# Power.net
KiCad netlist of a schematic drawn in Altium Designer
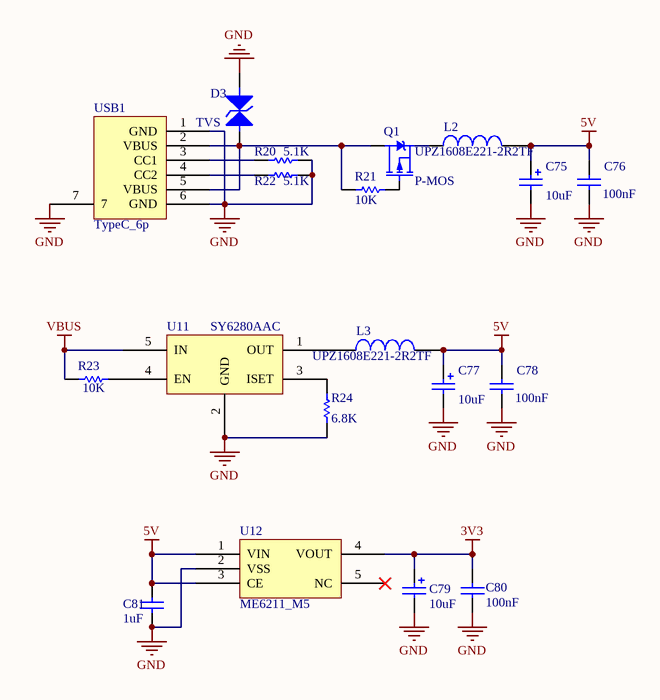
[diagram p0: Power.SchDoc]

(export (version "E")
  (design (tool "Eeschema 10.0.6"))
  (components
    (comp (ref "C75")
      (value "10uF")
      (footprint "电容:TAJ-A/3216")
      (description "Polarized Capacitor (Axial)")
      (fields (field (name "Comment") "Cap Pol2") (field (name "PUBLISHER") "Altium Limited"))
      (libsource (lib "Miscellaneous Devices") (part "Cap Pol2"))
    )
    (comp (ref "C76")
      (value "100nF")
      (footprint "C0603_M")
      (description "Capacitor")
      (fields (field (name "Comment") "Cap") (field (name "PUBLISHER") "Altium Limited"))
      (libsource (lib "Miscellaneous Devices") (part "Cap"))
    )
    (comp (ref "C77")
      (value "10uF")
      (footprint "电容:TAJ-A/3216")
      (description "Polarized Capacitor (Axial)")
      (fields (field (name "Comment") "Cap Pol2") (field (name "PUBLISHER") "Altium Limited"))
      (libsource (lib "Miscellaneous Devices") (part "Cap Pol2"))
    )
    (comp (ref "C78")
      (value "100nF")
      (footprint "C0603_M")
      (description "Capacitor")
      (fields (field (name "Comment") "Cap") (field (name "PUBLISHER") "Altium Limited"))
      (libsource (lib "Miscellaneous Devices") (part "Cap"))
    )
    (comp (ref "C79")
      (value "10uF")
      (footprint "TAJ-A/3216")
      (description "Polarized Capacitor (Axial)")
      (fields (field (name "Comment") "Cap Pol2") (field (name "PUBLISHER") "Altium Limited"))
      (libsource (lib "Miscellaneous Devices") (part "Cap Pol2"))
    )
    (comp (ref "C80")
      (value "100nF")
      (footprint "C0603_M")
      (description "Capacitor")
      (fields (field (name "Comment") "Cap") (field (name "PUBLISHER") "Altium Limited"))
      (libsource (lib "Miscellaneous Devices") (part "Cap"))
    )
    (comp (ref "C81")
      (value "1uF")
      (footprint "C0603_M")
      (description "Capacitor")
      (fields (field (name "Comment") "Cap") (field (name "PUBLISHER") "Altium Limited"))
      (libsource (lib "Miscellaneous Devices") (part "Cap"))
    )
    (comp (ref "D3")
      (value "TVS")
      (footprint "SOD-123")
      (description "双向瞬态抑制二极管")
      (libsource (lib "二极管") (part "TVS"))
    )
    (comp (ref "L2")
      (value "UPZ1608E221-2R2TF")
      (footprint "0603L")
      (description "INDUCTOR")
      (libsource (lib "电感") (part "INDUCTOR"))
    )
    (comp (ref "L3")
      (value "UPZ1608E221-2R2TF")
      (footprint "0603L")
      (description "INDUCTOR")
      (libsource (lib "电感") (part "INDUCTOR"))
    )
    (comp (ref "Q1")
      (value "P-MOS")
      (footprint "SOT23")
      (description "P沟道场效应管")
      (libsource (lib "MOS管") (part "P-MOS"))
    )
    (comp (ref "R20")
      (value "5.1K")
      (footprint "R0603_M")
      (description "Resistor")
      (fields (field (name "Comment") "Res1") (field (name "PUBLISHER") "Altium Limited"))
      (libsource (lib "Miscellaneous Devices") (part "Res1"))
    )
    (comp (ref "R21")
      (value "10K")
      (footprint "R0603_M")
      (description "Resistor")
      (fields (field (name "Comment") "Res1") (field (name "PUBLISHER") "Altium Limited"))
      (libsource (lib "Miscellaneous Devices") (part "Res1"))
    )
    (comp (ref "R22")
      (value "5.1K")
      (footprint "R0603_M")
      (description "Resistor")
      (fields (field (name "Comment") "Res1") (field (name "PUBLISHER") "Altium Limited"))
      (libsource (lib "Miscellaneous Devices") (part "Res1"))
    )
    (comp (ref "R23")
      (value "10K")
      (footprint "R0603_M")
      (description "Resistor")
      (fields (field (name "Comment") "Res1") (field (name "PUBLISHER") "Altium Limited"))
      (libsource (lib "Miscellaneous Devices") (part "Res1"))
    )
    (comp (ref "R24")
      (value "6.8K")
      (footprint "R0603_M")
      (description "Resistor")
      (fields (field (name "Comment") "Res1") (field (name "PUBLISHER") "Altium Limited"))
      (libsource (lib "Miscellaneous Devices") (part "Res1"))
    )
    (comp (ref "U11")
      (value "SY6280AAC")
      (footprint "SOT-23-5")
      (libsource (lib "MyIntLib") (part "SY6280AAC"))
    )
    (comp (ref "U12")
      (value "ME6211_M5")
      (footprint "SOT-23-5")
      (libsource (lib "MyIntLib") (part "ME6211_M5"))
    )
    (comp (ref "USB1")
      (value "TypeC_6p")
      (footprint "3.03-USB3.1 Type C-M.2-NGFF-HDMI-PCI-E接口:USB-C-SMD_6P")
      (libsource (lib "MyIntLib") (part "TypeC_6p"))
    )
  )
  (nets
    (net (code "1") (name "3V3") (class "Default")
      (node (ref "C79") (pin "1") (pinfunction "1_1") (pintype "passive"))
      (node (ref "C80") (pin "2") (pinfunction "2_2") (pintype "passive"))
      (node (ref "U12") (pin "4") (pinfunction "VOUT_4") (pintype "passive"))
    )
    (net (code "2") (name "5V") (class "Default")
      (node (ref "C75") (pin "1") (pinfunction "1_1") (pintype "passive"))
      (node (ref "C76") (pin "2") (pinfunction "2_2") (pintype "passive"))
      (node (ref "C77") (pin "1") (pinfunction "1_1") (pintype "passive"))
      (node (ref "C78") (pin "2") (pinfunction "2_2") (pintype "passive"))
      (node (ref "C81") (pin "2") (pinfunction "2_2") (pintype "passive"))
      (node (ref "L2") (pin "2") (pinfunction "2_2") (pintype "passive"))
      (node (ref "L3") (pin "2") (pinfunction "2_2") (pintype "passive"))
      (node (ref "U12") (pin "1") (pinfunction "VIN_1") (pintype "passive"))
      (node (ref "U12") (pin "3") (pinfunction "CE_3") (pintype "passive"))
    )
    (net (code "3") (name "GND") (class "Default")
      (node (ref "C75") (pin "2") (pinfunction "2_2") (pintype "passive"))
      (node (ref "C76") (pin "1") (pinfunction "1_1") (pintype "passive"))
      (node (ref "C77") (pin "2") (pinfunction "2_2") (pintype "passive"))
      (node (ref "C78") (pin "1") (pinfunction "1_1") (pintype "passive"))
      (node (ref "C79") (pin "2") (pinfunction "2_2") (pintype "passive"))
      (node (ref "C80") (pin "1") (pinfunction "1_1") (pintype "passive"))
      (node (ref "C81") (pin "1") (pinfunction "1_1") (pintype "passive"))
      (node (ref "D3") (pin "K") (pinfunction "K_K") (pintype "passive"))
      (node (ref "R20") (pin "1") (pinfunction "1_1") (pintype "passive"))
      (node (ref "R22") (pin "1") (pinfunction "1_1") (pintype "passive"))
      (node (ref "R24") (pin "2") (pinfunction "2_2") (pintype "passive"))
      (node (ref "U11") (pin "2") (pinfunction "GND_2") (pintype "passive"))
      (node (ref "U12") (pin "2") (pinfunction "VSS_2") (pintype "passive"))
      (node (ref "USB1") (pin "1") (pinfunction "GND_1") (pintype "passive"))
      (node (ref "USB1") (pin "6") (pinfunction "GND_6") (pintype "passive"))
      (node (ref "USB1") (pin "7") (pinfunction "7_7") (pintype "passive"))
    )
    (net (code "4") (name "Net-(D3-PadA)") (class "Default")
      (node (ref "D3") (pin "A") (pinfunction "A_A") (pintype "passive"))
      (node (ref "Q1") (pin "D") (pinfunction "D_D") (pintype "passive"))
      (node (ref "R21") (pin "1") (pinfunction "1_1") (pintype "passive"))
      (node (ref "USB1") (pin "2") (pinfunction "VBUS_2") (pintype "passive"))
      (node (ref "USB1") (pin "5") (pinfunction "VBUS_5") (pintype "passive"))
    )
    (net (code "5") (name "Net-(L2-Pad1)") (class "Default")
      (node (ref "L2") (pin "1") (pinfunction "1_1") (pintype "passive"))
      (node (ref "Q1") (pin "S") (pinfunction "S_S") (pintype "passive"))
    )
    (net (code "6") (name "Net-(Q1-PadG)") (class "Default")
      (node (ref "Q1") (pin "G") (pinfunction "G_G") (pintype "passive"))
      (node (ref "R21") (pin "2") (pinfunction "2_2") (pintype "passive"))
    )
    (net (code "7") (name "Net-(U11-EN)") (class "Default")
      (node (ref "R23") (pin "1") (pinfunction "1_1") (pintype "passive"))
      (node (ref "U11") (pin "4") (pinfunction "EN_4") (pintype "passive"))
    )
    (net (code "8") (name "Net-(U11-ISET)") (class "Default")
      (node (ref "R24") (pin "1") (pinfunction "1_1") (pintype "passive"))
      (node (ref "U11") (pin "3") (pinfunction "ISET_3") (pintype "passive"))
    )
    (net (code "9") (name "Net-(U11-OUT)") (class "Default")
      (node (ref "L3") (pin "1") (pinfunction "1_1") (pintype "passive"))
      (node (ref "U11") (pin "1") (pinfunction "OUT_1") (pintype "passive"))
    )
    (net (code "10") (name "Net-(USB1-CC1)") (class "Default")
      (node (ref "R20") (pin "2") (pinfunction "2_2") (pintype "passive"))
      (node (ref "USB1") (pin "3") (pinfunction "CC1_3") (pintype "passive"))
    )
    (net (code "11") (name "Net-(USB1-CC2)") (class "Default")
      (node (ref "R22") (pin "2") (pinfunction "2_2") (pintype "passive"))
      (node (ref "USB1") (pin "4") (pinfunction "CC2_4") (pintype "passive"))
    )
    (net (code "12") (name "VBUS") (class "Default")
      (node (ref "R23") (pin "2") (pinfunction "2_2") (pintype "passive"))
      (node (ref "U11") (pin "5") (pinfunction "IN_5") (pintype "passive"))
    )
    (net (code "13") (name "unconnected-(U12-NC-Pad5)") (class "Default")
      (node (ref "U12") (pin "5") (pinfunction "NC_5") (pintype "passive+no_connect"))
    )
  )
)
